# displayBoard-v2.net
KiCad netlist of a schematic drawn in EAGLE
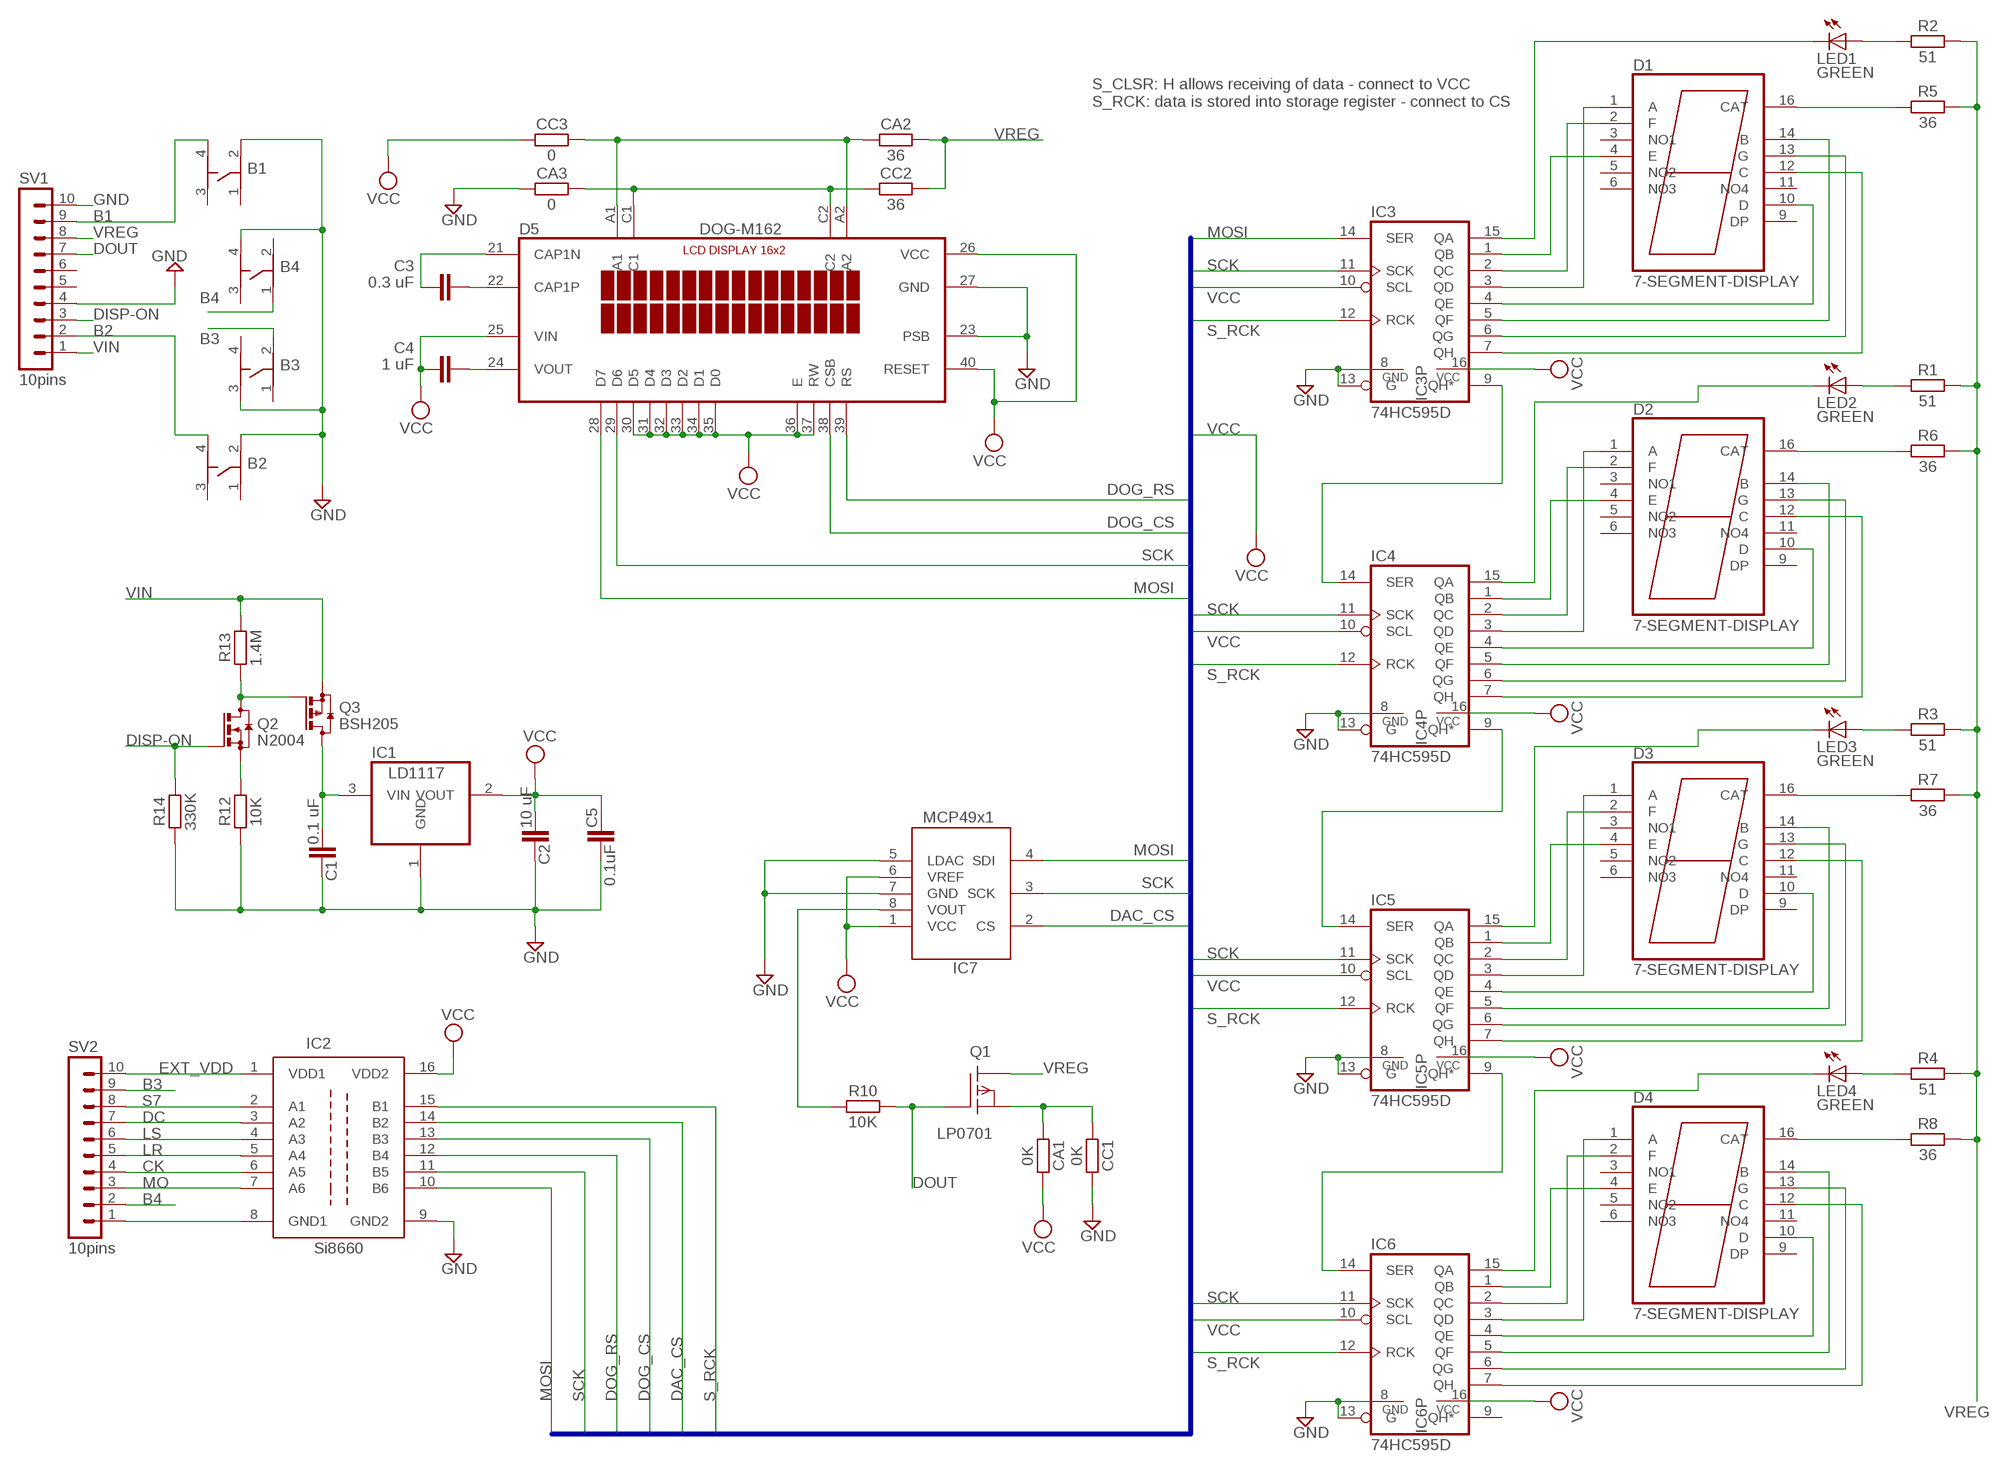
[diagram p0: schematic, sheet 1]

(export (version "E")
  (design (tool "Eeschema 10.0.6"))
  (components
    (comp (ref "B1")
      (value "BUTTON-D6X")
      (footprint "eagle-import:BUTTON-D6X")
      (libsource (lib "eagle-import") (part "BUTTON-D6X"))
    )
    (comp (ref "B2")
      (value "BUTTON-D6X")
      (footprint "eagle-import:BUTTON-D6X")
      (libsource (lib "eagle-import") (part "BUTTON-D6X"))
    )
    (comp (ref "B3")
      (value "BUTTON-D6X")
      (footprint "eagle-import:BUTTON-D6X")
      (libsource (lib "eagle-import") (part "BUTTON-D6X"))
    )
    (comp (ref "B4")
      (value "BUTTON-D6X")
      (footprint "eagle-import:BUTTON-D6X")
      (libsource (lib "eagle-import") (part "BUTTON-D6X"))
    )
    (comp (ref "C1")
      (value "0.1 uF")
      (footprint "eagle-import:C1206")
      (libsource (lib "eagle-import") (part "C-EUC1206"))
    )
    (comp (ref "C2")
      (value "10 uF")
      (footprint "eagle-import:C1206")
      (libsource (lib "eagle-import") (part "C-EUC1206"))
    )
    (comp (ref "C3")
      (value "0.3 uF")
      (footprint "eagle-import:C1206")
      (libsource (lib "eagle-import") (part "C-EUC1206"))
    )
    (comp (ref "C4")
      (value "1 uF")
      (footprint "eagle-import:C1206")
      (libsource (lib "eagle-import") (part "C-EUC1206"))
    )
    (comp (ref "C5")
      (value "0.1uF")
      (footprint "eagle-import:C1206")
      (libsource (lib "eagle-import") (part "C-EUC1206"))
    )
    (comp (ref "CA1")
      (value "0K")
      (footprint "eagle-import:R1206")
      (libsource (lib "eagle-import") (part "R-EU_R1206"))
    )
    (comp (ref "CA2")
      (value "36")
      (footprint "eagle-import:R1206")
      (libsource (lib "eagle-import") (part "R-EU_R1206"))
    )
    (comp (ref "CA3")
      (value "0")
      (footprint "eagle-import:R1206")
      (libsource (lib "eagle-import") (part "R-EU_R1206"))
    )
    (comp (ref "CC1")
      (value "0K")
      (footprint "eagle-import:R1206")
      (libsource (lib "eagle-import") (part "R-EU_R1206"))
    )
    (comp (ref "CC2")
      (value "36")
      (footprint "eagle-import:R1206")
      (libsource (lib "eagle-import") (part "R-EU_R1206"))
    )
    (comp (ref "CC3")
      (value "0")
      (footprint "eagle-import:R1206")
      (libsource (lib "eagle-import") (part "R-EU_R1206"))
    )
    (comp (ref "D1")
      (value "7-SEGMENT-DISPLAY")
      (footprint "eagle-import:LDS-A812")
      (libsource (lib "eagle-import") (part "7-SEGMENT-DISPLAY"))
    )
    (comp (ref "D2")
      (value "7-SEGMENT-DISPLAY")
      (footprint "eagle-import:LDS-A812")
      (libsource (lib "eagle-import") (part "7-SEGMENT-DISPLAY"))
    )
    (comp (ref "D3")
      (value "7-SEGMENT-DISPLAY")
      (footprint "eagle-import:LDS-A812")
      (libsource (lib "eagle-import") (part "7-SEGMENT-DISPLAY"))
    )
    (comp (ref "D4")
      (value "7-SEGMENT-DISPLAY")
      (footprint "eagle-import:LDS-A812")
      (libsource (lib "eagle-import") (part "7-SEGMENT-DISPLAY"))
    )
    (comp (ref "D5")
      (value "DOG-M162")
      (footprint "eagle-import:DOGM162")
      (libsource (lib "eagle-import") (part "DOG-M162"))
    )
    (comp (ref "IC1")
      (value "LD1117")
      (footprint "eagle-import:SOT223")
      (fields (field (name "MPN") "REG1117"))
      (libsource (lib "eagle-import") (part "REG1117"))
    )
    (comp (ref "IC2")
      (value "SI-8660")
      (footprint "eagle-import:SOP-16")
      (libsource (lib "eagle-import") (part "SI-8660"))
    )
    (comp (ref "IC3")
      (value "74HC595D")
      (footprint "eagle-import:SO16")
      (libsource (lib "eagle-import") (part "74595DHC"))
    )
    (comp (ref "IC4")
      (value "74HC595D")
      (footprint "eagle-import:SO16")
      (libsource (lib "eagle-import") (part "74595DHC"))
    )
    (comp (ref "IC5")
      (value "74HC595D")
      (footprint "eagle-import:SO16")
      (libsource (lib "eagle-import") (part "74595DHC"))
    )
    (comp (ref "IC6")
      (value "74HC595D")
      (footprint "eagle-import:SO16")
      (libsource (lib "eagle-import") (part "74595DHC"))
    )
    (comp (ref "IC7")
      (value "MCP4921")
      (footprint "eagle-import:MSOP-8")
      (libsource (lib "eagle-import") (part "MCP4901"))
    )
    (comp (ref "LED1")
      (value "GREEN")
      (footprint "eagle-import:LED3MM")
      (libsource (lib "eagle-import") (part "LED3MM"))
    )
    (comp (ref "LED2")
      (value "GREEN")
      (footprint "eagle-import:LED3MM")
      (libsource (lib "eagle-import") (part "LED3MM"))
    )
    (comp (ref "LED3")
      (value "GREEN")
      (footprint "eagle-import:LED3MM")
      (libsource (lib "eagle-import") (part "LED3MM"))
    )
    (comp (ref "LED4")
      (value "GREEN")
      (footprint "eagle-import:LED3MM")
      (libsource (lib "eagle-import") (part "LED3MM"))
    )
    (comp (ref "Q1")
      (value "LP0701")
      (footprint "eagle-import:TO-92")
      (libsource (lib "eagle-import") (part "LP0701N3"))
    )
    (comp (ref "Q2")
      (value "N2004")
      (footprint "eagle-import:SOT23")
      (libsource (lib "eagle-import") (part "BSS123"))
    )
    (comp (ref "Q3")
      (value "BSH205")
      (footprint "eagle-import:SOT23")
      (libsource (lib "eagle-import") (part "BSS84"))
    )
    (comp (ref "R1")
      (value "51")
      (footprint "eagle-import:R1206")
      (libsource (lib "eagle-import") (part "R-EU_R1206"))
    )
    (comp (ref "R2")
      (value "51")
      (footprint "eagle-import:R1206")
      (libsource (lib "eagle-import") (part "R-EU_R1206"))
    )
    (comp (ref "R3")
      (value "51")
      (footprint "eagle-import:R1206")
      (libsource (lib "eagle-import") (part "R-EU_R1206"))
    )
    (comp (ref "R4")
      (value "51")
      (footprint "eagle-import:R1206")
      (libsource (lib "eagle-import") (part "R-EU_R1206"))
    )
    (comp (ref "R5")
      (value "36")
      (footprint "eagle-import:R1206")
      (libsource (lib "eagle-import") (part "R-EU_R1206"))
    )
    (comp (ref "R6")
      (value "36")
      (footprint "eagle-import:R1206")
      (libsource (lib "eagle-import") (part "R-EU_R1206"))
    )
    (comp (ref "R7")
      (value "36")
      (footprint "eagle-import:R1206")
      (libsource (lib "eagle-import") (part "R-EU_R1206"))
    )
    (comp (ref "R8")
      (value "36")
      (footprint "eagle-import:R1206")
      (libsource (lib "eagle-import") (part "R-EU_R1206"))
    )
    (comp (ref "R10")
      (value "10K")
      (footprint "eagle-import:R1206")
      (libsource (lib "eagle-import") (part "R-EU_R1206"))
    )
    (comp (ref "R12")
      (value "10K")
      (footprint "eagle-import:R1206")
      (libsource (lib "eagle-import") (part "R-EU_R1206"))
    )
    (comp (ref "R13")
      (value "1.4M")
      (footprint "eagle-import:R1206")
      (libsource (lib "eagle-import") (part "R-EU_R1206"))
    )
    (comp (ref "R14")
      (value "330K")
      (footprint "eagle-import:R1206")
      (libsource (lib "eagle-import") (part "R-EU_R1206"))
    )
    (comp (ref "SV1")
      (value "10pins")
      (footprint "eagle-import:MA10-1")
      (libsource (lib "eagle-import") (part "MA10-1"))
    )
    (comp (ref "SV2")
      (value "10pins")
      (footprint "eagle-import:MA10-1")
      (libsource (lib "eagle-import") (part "MA10-1"))
    )
  )
  (nets
    (net (code "1") (name "/B1") (class "Default")
      (node (ref "B1") (pin "4") (pinfunction "4_4") (pintype "bidirectional"))
      (node (ref "SV1") (pin "9") (pinfunction "9_9") (pintype "passive"))
    )
    (net (code "2") (name "/B2") (class "Default")
      (node (ref "B2") (pin "4") (pinfunction "4_4") (pintype "bidirectional"))
      (node (ref "SV1") (pin "2") (pinfunction "2_2") (pintype "passive"))
    )
    (net (code "3") (name "/B3") (class "Default")
      (node (ref "B3") (pin "2") (pinfunction "2_2") (pintype "bidirectional"))
      (node (ref "SV2") (pin "9") (pinfunction "9_9") (pintype "passive"))
    )
    (net (code "4") (name "/B4") (class "Default")
      (node (ref "B4") (pin "1") (pinfunction "1_1") (pintype "bidirectional"))
      (node (ref "SV2") (pin "2") (pinfunction "2_2") (pintype "passive"))
    )
    (net (code "5") (name "/CK") (class "Default")
      (node (ref "IC2") (pin "6") (pinfunction "A5_6") (pintype "bidirectional"))
      (node (ref "SV2") (pin "4") (pinfunction "4_4") (pintype "passive"))
    )
    (net (code "6") (name "/DAC_CS") (class "Default")
      (node (ref "IC2") (pin "14") (pinfunction "B2_14") (pintype "bidirectional"))
      (node (ref "IC7") (pin "2") (pinfunction "CS_2") (pintype "bidirectional"))
    )
    (net (code "7") (name "/DC") (class "Default")
      (node (ref "IC2") (pin "3") (pinfunction "A2_3") (pintype "bidirectional"))
      (node (ref "SV2") (pin "7") (pinfunction "7_7") (pintype "passive"))
    )
    (net (code "8") (name "/DISP-ON") (class "Default")
      (node (ref "Q2") (pin "1") (pinfunction "G_1") (pintype "passive"))
      (node (ref "R14") (pin "2") (pinfunction "2_2") (pintype "passive"))
      (node (ref "SV1") (pin "3") (pinfunction "3_3") (pintype "passive"))
    )
    (net (code "9") (name "/DOG_CS") (class "Default")
      (node (ref "D5") (pin "38") (pinfunction "CSB_38") (pintype "bidirectional"))
      (node (ref "IC2") (pin "13") (pinfunction "B3_13") (pintype "bidirectional"))
    )
    (net (code "10") (name "/DOG_RS") (class "Default")
      (node (ref "D5") (pin "39") (pinfunction "RS_39") (pintype "bidirectional"))
      (node (ref "IC2") (pin "12") (pinfunction "B4_12") (pintype "bidirectional"))
    )
    (net (code "11") (name "/DOUT") (class "Default")
      (node (ref "Q1") (pin "2") (pinfunction "G_2") (pintype "passive"))
      (node (ref "R10") (pin "2") (pinfunction "2_2") (pintype "passive"))
      (node (ref "SV1") (pin "7") (pinfunction "7_7") (pintype "passive"))
    )
    (net (code "12") (name "/EXT_VDD") (class "Default")
      (node (ref "IC2") (pin "1") (pinfunction "VDD1_1") (pintype "bidirectional"))
      (node (ref "SV2") (pin "10") (pinfunction "10_10") (pintype "passive"))
    )
    (net (code "13") (name "/LR") (class "Default")
      (node (ref "IC2") (pin "5") (pinfunction "A4_5") (pintype "bidirectional"))
      (node (ref "SV2") (pin "5") (pinfunction "5_5") (pintype "passive"))
    )
    (net (code "14") (name "/LS") (class "Default")
      (node (ref "IC2") (pin "4") (pinfunction "A3_4") (pintype "bidirectional"))
      (node (ref "SV2") (pin "6") (pinfunction "6_6") (pintype "passive"))
    )
    (net (code "15") (name "/MO") (class "Default")
      (node (ref "IC2") (pin "7") (pinfunction "A6_7") (pintype "bidirectional"))
      (node (ref "SV2") (pin "3") (pinfunction "3_3") (pintype "passive"))
    )
    (net (code "16") (name "/MOSI") (class "Default")
      (node (ref "D5") (pin "28") (pinfunction "D7_28") (pintype "bidirectional"))
      (node (ref "IC2") (pin "10") (pinfunction "B6_10") (pintype "bidirectional"))
      (node (ref "IC3") (pin "14") (pinfunction "SER_14") (pintype "input"))
      (node (ref "IC7") (pin "4") (pinfunction "SDI_4") (pintype "bidirectional"))
    )
    (net (code "17") (name "/S7") (class "Default")
      (node (ref "IC2") (pin "2") (pinfunction "A1_2") (pintype "bidirectional"))
      (node (ref "SV2") (pin "8") (pinfunction "8_8") (pintype "passive"))
    )
    (net (code "18") (name "/SCK") (class "Default")
      (node (ref "D5") (pin "29") (pinfunction "D6_29") (pintype "bidirectional"))
      (node (ref "IC2") (pin "11") (pinfunction "B5_11") (pintype "bidirectional"))
      (node (ref "IC3") (pin "11") (pinfunction "SCK_11") (pintype "input"))
      (node (ref "IC4") (pin "11") (pinfunction "SCK_11") (pintype "input"))
      (node (ref "IC5") (pin "11") (pinfunction "SCK_11") (pintype "input"))
      (node (ref "IC6") (pin "11") (pinfunction "SCK_11") (pintype "input"))
      (node (ref "IC7") (pin "3") (pinfunction "SCK_3") (pintype "bidirectional"))
    )
    (net (code "19") (name "/S_RCK") (class "Default")
      (node (ref "IC2") (pin "15") (pinfunction "B1_15") (pintype "bidirectional"))
      (node (ref "IC3") (pin "12") (pinfunction "RCK_12") (pintype "input"))
      (node (ref "IC4") (pin "12") (pinfunction "RCK_12") (pintype "input"))
      (node (ref "IC5") (pin "12") (pinfunction "RCK_12") (pintype "input"))
      (node (ref "IC6") (pin "12") (pinfunction "RCK_12") (pintype "input"))
    )
    (net (code "20") (name "/VIN") (class "Default")
      (node (ref "Q3") (pin "2") (pinfunction "S_2") (pintype "passive"))
      (node (ref "R13") (pin "2") (pinfunction "2_2") (pintype "passive"))
      (node (ref "SV1") (pin "1") (pinfunction "1_1") (pintype "passive"))
    )
    (net (code "21") (name "/VREG") (class "Default")
      (node (ref "CA2") (pin "2") (pinfunction "2_2") (pintype "passive"))
      (node (ref "CC2") (pin "2") (pinfunction "2_2") (pintype "passive"))
      (node (ref "Q1") (pin "3") (pinfunction "D_3") (pintype "passive"))
      (node (ref "R1") (pin "2") (pinfunction "2_2") (pintype "passive"))
      (node (ref "R2") (pin "2") (pinfunction "2_2") (pintype "passive"))
      (node (ref "R3") (pin "2") (pinfunction "2_2") (pintype "passive"))
      (node (ref "R4") (pin "2") (pinfunction "2_2") (pintype "passive"))
      (node (ref "R5") (pin "2") (pinfunction "2_2") (pintype "passive"))
      (node (ref "R6") (pin "2") (pinfunction "2_2") (pintype "passive"))
      (node (ref "R7") (pin "2") (pinfunction "2_2") (pintype "passive"))
      (node (ref "R8") (pin "2") (pinfunction "2_2") (pintype "passive"))
      (node (ref "SV1") (pin "8") (pinfunction "8_8") (pintype "passive"))
    )
    (net (code "22") (name "GND") (class "Default")
      (node (ref "B1") (pin "2") (pinfunction "2_2") (pintype "bidirectional"))
      (node (ref "B2") (pin "2") (pinfunction "2_2") (pintype "bidirectional"))
      (node (ref "B3") (pin "3") (pinfunction "3_3") (pintype "bidirectional"))
      (node (ref "B4") (pin "4") (pinfunction "4_4") (pintype "bidirectional"))
      (node (ref "C1") (pin "1") (pinfunction "1_1") (pintype "passive"))
      (node (ref "C2") (pin "1") (pinfunction "1_1") (pintype "passive"))
      (node (ref "C5") (pin "2") (pinfunction "2_2") (pintype "passive"))
      (node (ref "CA3") (pin "1") (pinfunction "1_1") (pintype "passive"))
      (node (ref "CC1") (pin "2") (pinfunction "2_2") (pintype "passive"))
      (node (ref "D5") (pin "23") (pinfunction "PSB_23") (pintype "bidirectional"))
      (node (ref "D5") (pin "27") (pinfunction "GND_27") (pintype "power_in"))
      (node (ref "IC1") (pin "1") (pinfunction "GND_1") (pintype "power_in"))
      (node (ref "IC2") (pin "9") (pinfunction "GND2_9") (pintype "bidirectional"))
      (node (ref "IC3") (pin "13") (pinfunction "G_13") (pintype "input"))
      (node (ref "IC3") (pin "8") (pinfunction "GND_8") (pintype "power_in"))
      (node (ref "IC4") (pin "13") (pinfunction "G_13") (pintype "input"))
      (node (ref "IC4") (pin "8") (pinfunction "GND_8") (pintype "power_in"))
      (node (ref "IC5") (pin "13") (pinfunction "G_13") (pintype "input"))
      (node (ref "IC5") (pin "8") (pinfunction "GND_8") (pintype "power_in"))
      (node (ref "IC6") (pin "13") (pinfunction "G_13") (pintype "input"))
      (node (ref "IC6") (pin "8") (pinfunction "GND_8") (pintype "power_in"))
      (node (ref "IC7") (pin "5") (pinfunction "LDAC_5") (pintype "bidirectional"))
      (node (ref "IC7") (pin "7") (pinfunction "GND_7") (pintype "power_in"))
      (node (ref "R12") (pin "1") (pinfunction "1_1") (pintype "passive"))
      (node (ref "R14") (pin "1") (pinfunction "1_1") (pintype "passive"))
      (node (ref "SV1") (pin "10") (pinfunction "10_10") (pintype "passive"))
      (node (ref "SV1") (pin "4") (pinfunction "4_4") (pintype "passive"))
    )
    (net (code "23") (name "Net-(CA2-Pad1)") (class "Default")
      (node (ref "CA2") (pin "1") (pinfunction "1_1") (pintype "passive"))
      (node (ref "CC3") (pin "2") (pinfunction "2_2") (pintype "passive"))
      (node (ref "D5") (pin "A1") (pinfunction "A1_A1") (pintype "bidirectional"))
      (node (ref "D5") (pin "A2") (pinfunction "A2_A2") (pintype "bidirectional"))
    )
    (net (code "24") (name "Net-(CA3-Pad2)") (class "Default")
      (node (ref "CA3") (pin "2") (pinfunction "2_2") (pintype "passive"))
      (node (ref "CC2") (pin "1") (pinfunction "1_1") (pintype "passive"))
      (node (ref "D5") (pin "C1") (pinfunction "C1_C1") (pintype "bidirectional"))
      (node (ref "D5") (pin "C2") (pinfunction "C2_C2") (pintype "bidirectional"))
    )
    (net (code "25") (name "Net-(D1-A)") (class "Default")
      (node (ref "D1") (pin "1") (pinfunction "A_1") (pintype "input"))
      (node (ref "IC3") (pin "3") (pinfunction "QD_3") (pintype "tri_state"))
    )
    (net (code "26") (name "Net-(D1-B)") (class "Default")
      (node (ref "D1") (pin "14") (pinfunction "B_14") (pintype "input"))
      (node (ref "IC3") (pin "5") (pinfunction "QF_5") (pintype "tri_state"))
    )
    (net (code "27") (name "Net-(D1-C)") (class "Default")
      (node (ref "D1") (pin "12") (pinfunction "C_12") (pintype "input"))
      (node (ref "IC3") (pin "7") (pinfunction "QH_7") (pintype "tri_state"))
    )
    (net (code "28") (name "Net-(D1-CAT)") (class "Default")
      (node (ref "D1") (pin "16") (pinfunction "CAT_16") (pintype "bidirectional"))
      (node (ref "R5") (pin "1") (pinfunction "1_1") (pintype "passive"))
    )
    (net (code "29") (name "Net-(D1-D)") (class "Default")
      (node (ref "D1") (pin "10") (pinfunction "D_10") (pintype "input"))
      (node (ref "IC3") (pin "4") (pinfunction "QE_4") (pintype "tri_state"))
    )
    (net (code "30") (name "Net-(D1-E)") (class "Default")
      (node (ref "D1") (pin "4") (pinfunction "E_4") (pintype "input"))
      (node (ref "IC3") (pin "1") (pinfunction "QB_1") (pintype "tri_state"))
    )
    (net (code "31") (name "Net-(D1-F)") (class "Default")
      (node (ref "D1") (pin "2") (pinfunction "F_2") (pintype "input"))
      (node (ref "IC3") (pin "2") (pinfunction "QC_2") (pintype "tri_state"))
    )
    (net (code "32") (name "Net-(D1-G)") (class "Default")
      (node (ref "D1") (pin "13") (pinfunction "G_13") (pintype "input"))
      (node (ref "IC3") (pin "6") (pinfunction "QG_6") (pintype "tri_state"))
    )
    (net (code "33") (name "Net-(D2-A)") (class "Default")
      (node (ref "D2") (pin "1") (pinfunction "A_1") (pintype "input"))
      (node (ref "IC4") (pin "3") (pinfunction "QD_3") (pintype "tri_state"))
    )
    (net (code "34") (name "Net-(D2-B)") (class "Default")
      (node (ref "D2") (pin "14") (pinfunction "B_14") (pintype "input"))
      (node (ref "IC4") (pin "5") (pinfunction "QF_5") (pintype "tri_state"))
    )
    (net (code "35") (name "Net-(D2-C)") (class "Default")
      (node (ref "D2") (pin "12") (pinfunction "C_12") (pintype "input"))
      (node (ref "IC4") (pin "7") (pinfunction "QH_7") (pintype "tri_state"))
    )
    (net (code "36") (name "Net-(D2-CAT)") (class "Default")
      (node (ref "D2") (pin "16") (pinfunction "CAT_16") (pintype "bidirectional"))
      (node (ref "R6") (pin "1") (pinfunction "1_1") (pintype "passive"))
    )
    (net (code "37") (name "Net-(D2-D)") (class "Default")
      (node (ref "D2") (pin "10") (pinfunction "D_10") (pintype "input"))
      (node (ref "IC4") (pin "4") (pinfunction "QE_4") (pintype "tri_state"))
    )
    (net (code "38") (name "Net-(D2-E)") (class "Default")
      (node (ref "D2") (pin "4") (pinfunction "E_4") (pintype "input"))
      (node (ref "IC4") (pin "1") (pinfunction "QB_1") (pintype "tri_state"))
    )
    (net (code "39") (name "Net-(D2-F)") (class "Default")
      (node (ref "D2") (pin "2") (pinfunction "F_2") (pintype "input"))
      (node (ref "IC4") (pin "2") (pinfunction "QC_2") (pintype "tri_state"))
    )
    (net (code "40") (name "Net-(D2-G)") (class "Default")
      (node (ref "D2") (pin "13") (pinfunction "G_13") (pintype "input"))
      (node (ref "IC4") (pin "6") (pinfunction "QG_6") (pintype "tri_state"))
    )
    (net (code "41") (name "Net-(D3-A)") (class "Default")
      (node (ref "D3") (pin "1") (pinfunction "A_1") (pintype "input"))
      (node (ref "IC5") (pin "3") (pinfunction "QD_3") (pintype "tri_state"))
    )
    (net (code "42") (name "Net-(D3-B)") (class "Default")
      (node (ref "D3") (pin "14") (pinfunction "B_14") (pintype "input"))
      (node (ref "IC5") (pin "5") (pinfunction "QF_5") (pintype "tri_state"))
    )
    (net (code "43") (name "Net-(D3-C)") (class "Default")
      (node (ref "D3") (pin "12") (pinfunction "C_12") (pintype "input"))
      (node (ref "IC5") (pin "7") (pinfunction "QH_7") (pintype "tri_state"))
    )
    (net (code "44") (name "Net-(D3-CAT)") (class "Default")
      (node (ref "D3") (pin "16") (pinfunction "CAT_16") (pintype "bidirectional"))
      (node (ref "R7") (pin "1") (pinfunction "1_1") (pintype "passive"))
    )
    (net (code "45") (name "Net-(D3-D)") (class "Default")
      (node (ref "D3") (pin "10") (pinfunction "D_10") (pintype "input"))
      (node (ref "IC5") (pin "4") (pinfunction "QE_4") (pintype "tri_state"))
    )
    (net (code "46") (name "Net-(D3-E)") (class "Default")
      (node (ref "D3") (pin "4") (pinfunction "E_4") (pintype "input"))
      (node (ref "IC5") (pin "1") (pinfunction "QB_1") (pintype "tri_state"))
    )
    (net (code "47") (name "Net-(D3-F)") (class "Default")
      (node (ref "D3") (pin "2") (pinfunction "F_2") (pintype "input"))
      (node (ref "IC5") (pin "2") (pinfunction "QC_2") (pintype "tri_state"))
    )
    (net (code "48") (name "Net-(D3-G)") (class "Default")
      (node (ref "D3") (pin "13") (pinfunction "G_13") (pintype "input"))
      (node (ref "IC5") (pin "6") (pinfunction "QG_6") (pintype "tri_state"))
    )
    (net (code "49") (name "Net-(D4-A)") (class "Default")
      (node (ref "D4") (pin "1") (pinfunction "A_1") (pintype "input"))
      (node (ref "IC6") (pin "3") (pinfunction "QD_3") (pintype "tri_state"))
    )
    (net (code "50") (name "Net-(D4-B)") (class "Default")
      (node (ref "D4") (pin "14") (pinfunction "B_14") (pintype "input"))
      (node (ref "IC6") (pin "5") (pinfunction "QF_5") (pintype "tri_state"))
    )
    (net (code "51") (name "Net-(D4-C)") (class "Default")
      (node (ref "D4") (pin "12") (pinfunction "C_12") (pintype "input"))
      (node (ref "IC6") (pin "7") (pinfunction "QH_7") (pintype "tri_state"))
    )
    (net (code "52") (name "Net-(D4-CAT)") (class "Default")
      (node (ref "D4") (pin "16") (pinfunction "CAT_16") (pintype "bidirectional"))
      (node (ref "R8") (pin "1") (pinfunction "1_1") (pintype "passive"))
    )
    (net (code "53") (name "Net-(D4-D)") (class "Default")
      (node (ref "D4") (pin "10") (pinfunction "D_10") (pintype "input"))
      (node (ref "IC6") (pin "4") (pinfunction "QE_4") (pintype "tri_state"))
    )
    (net (code "54") (name "Net-(D4-E)") (class "Default")
      (node (ref "D4") (pin "4") (pinfunction "E_4") (pintype "input"))
      (node (ref "IC6") (pin "1") (pinfunction "QB_1") (pintype "tri_state"))
    )
    (net (code "55") (name "Net-(D4-F)") (class "Default")
      (node (ref "D4") (pin "2") (pinfunction "F_2") (pintype "input"))
      (node (ref "IC6") (pin "2") (pinfunction "QC_2") (pintype "tri_state"))
    )
    (net (code "56") (name "Net-(D4-G)") (class "Default")
      (node (ref "D4") (pin "13") (pinfunction "G_13") (pintype "input"))
      (node (ref "IC6") (pin "6") (pinfunction "QG_6") (pintype "tri_state"))
    )
    (net (code "57") (name "Net-(D5-CAP1N)") (class "Default")
      (node (ref "C3") (pin "1") (pinfunction "1_1") (pintype "passive"))
      (node (ref "D5") (pin "21") (pinfunction "CAP1N_21") (pintype "bidirectional"))
    )
    (net (code "58") (name "Net-(D5-CAP1P)") (class "Default")
      (node (ref "C3") (pin "2") (pinfunction "2_2") (pintype "passive"))
      (node (ref "D5") (pin "22") (pinfunction "CAP1P_22") (pintype "bidirectional"))
    )
    (net (code "59") (name "Net-(D5-VOUT)") (class "Default")
      (node (ref "C4") (pin "1") (pinfunction "1_1") (pintype "passive"))
      (node (ref "D5") (pin "24") (pinfunction "VOUT_24") (pintype "bidirectional"))
    )
    (net (code "60") (name "Net-(IC1-VIN)") (class "Default")
      (node (ref "C1") (pin "2") (pinfunction "2_2") (pintype "passive"))
      (node (ref "IC1") (pin "3") (pinfunction "VIN_3") (pintype "input"))
      (node (ref "Q3") (pin "3") (pinfunction "D_3") (pintype "passive"))
    )
    (net (code "61") (name "Net-(IC2-GND1)") (class "Default")
      (node (ref "IC2") (pin "8") (pinfunction "GND1_8") (pintype "bidirectional"))
      (node (ref "SV2") (pin "1") (pinfunction "1_1") (pintype "passive"))
    )
    (net (code "62") (name "Net-(IC3A-QA)") (class "Default")
      (node (ref "IC3") (pin "15") (pinfunction "QA_15") (pintype "tri_state"))
      (node (ref "LED1") (pin "K") (pinfunction "C_K") (pintype "passive"))
    )
    (net (code "63") (name "Net-(IC3A-QH*)") (class "Default")
      (node (ref "IC3") (pin "9") (pinfunction "QH*_9") (pintype "tri_state"))
      (node (ref "IC4") (pin "14") (pinfunction "SER_14") (pintype "input"))
    )
    (net (code "64") (name "Net-(IC4A-QA)") (class "Default")
      (node (ref "IC4") (pin "15") (pinfunction "QA_15") (pintype "tri_state"))
      (node (ref "LED2") (pin "K") (pinfunction "C_K") (pintype "passive"))
    )
    (net (code "65") (name "Net-(IC4A-QH*)") (class "Default")
      (node (ref "IC4") (pin "9") (pinfunction "QH*_9") (pintype "tri_state"))
      (node (ref "IC5") (pin "14") (pinfunction "SER_14") (pintype "input"))
    )
    (net (code "66") (name "Net-(IC5A-QA)") (class "Default")
      (node (ref "IC5") (pin "15") (pinfunction "QA_15") (pintype "tri_state"))
      (node (ref "LED3") (pin "K") (pinfunction "C_K") (pintype "passive"))
    )
    (net (code "67") (name "Net-(IC5A-QH*)") (class "Default")
      (node (ref "IC5") (pin "9") (pinfunction "QH*_9") (pintype "tri_state"))
      (node (ref "IC6") (pin "14") (pinfunction "SER_14") (pintype "input"))
    )
    (net (code "68") (name "Net-(IC6A-QA)") (class "Default")
      (node (ref "IC6") (pin "15") (pinfunction "QA_15") (pintype "tri_state"))
      (node (ref "LED4") (pin "K") (pinfunction "C_K") (pintype "passive"))
    )
    (net (code "69") (name "Net-(IC7-VOUT)") (class "Default")
      (node (ref "IC7") (pin "8") (pinfunction "VOUT_8") (pintype "bidirectional"))
      (node (ref "R10") (pin "1") (pinfunction "1_1") (pintype "passive"))
    )
    (net (code "70") (name "Net-(LED1-PadA)") (class "Default")
      (node (ref "LED1") (pin "A") (pinfunction "A_A") (pintype "passive"))
      (node (ref "R2") (pin "1") (pinfunction "1_1") (pintype "passive"))
    )
    (net (code "71") (name "Net-(LED2-PadA)") (class "Default")
      (node (ref "LED2") (pin "A") (pinfunction "A_A") (pintype "passive"))
      (node (ref "R1") (pin "1") (pinfunction "1_1") (pintype "passive"))
    )
    (net (code "72") (name "Net-(LED3-PadA)") (class "Default")
      (node (ref "LED3") (pin "A") (pinfunction "A_A") (pintype "passive"))
      (node (ref "R3") (pin "1") (pinfunction "1_1") (pintype "passive"))
    )
    (net (code "73") (name "Net-(LED4-PadA)") (class "Default")
      (node (ref "LED4") (pin "A") (pinfunction "A_A") (pintype "passive"))
      (node (ref "R4") (pin "1") (pinfunction "1_1") (pintype "passive"))
    )
    (net (code "74") (name "Net-(Q1-S)") (class "Default")
      (node (ref "CA1") (pin "1") (pinfunction "1_1") (pintype "passive"))
      (node (ref "CC1") (pin "1") (pinfunction "1_1") (pintype "passive"))
      (node (ref "Q1") (pin "1") (pinfunction "S_1") (pintype "passive"))
    )
    (net (code "75") (name "Net-(Q2-D)") (class "Default")
      (node (ref "Q2") (pin "3") (pinfunction "D_3") (pintype "passive"))
      (node (ref "Q3") (pin "1") (pinfunction "G_1") (pintype "passive"))
      (node (ref "R13") (pin "1") (pinfunction "1_1") (pintype "passive"))
    )
    (net (code "76") (name "Net-(Q2-S)") (class "Default")
      (node (ref "Q2") (pin "2") (pinfunction "S_2") (pintype "passive"))
      (node (ref "R12") (pin "2") (pinfunction "2_2") (pintype "passive"))
    )
    (net (code "77") (name "VCC") (class "Default")
      (node (ref "C2") (pin "2") (pinfunction "2_2") (pintype "passive"))
      (node (ref "C4") (pin "2") (pinfunction "2_2") (pintype "passive"))
      (node (ref "C5") (pin "1") (pinfunction "1_1") (pintype "passive"))
      (node (ref "CA1") (pin "2") (pinfunction "2_2") (pintype "passive"))
      (node (ref "CC3") (pin "1") (pinfunction "1_1") (pintype "passive"))
      (node (ref "D5") (pin "25") (pinfunction "VIN_25") (pintype "bidirectional"))
      (node (ref "D5") (pin "26") (pinfunction "VCC_26") (pintype "power_in"))
      (node (ref "D5") (pin "30") (pinfunction "D5_30") (pintype "bidirectional"))
      (node (ref "D5") (pin "31") (pinfunction "D4_31") (pintype "bidirectional"))
      (node (ref "D5") (pin "32") (pinfunction "D3_32") (pintype "bidirectional"))
      (node (ref "D5") (pin "33") (pinfunction "D2_33") (pintype "bidirectional"))
      (node (ref "D5") (pin "34") (pinfunction "D1_34") (pintype "bidirectional"))
      (node (ref "D5") (pin "35") (pinfunction "D0_35") (pintype "bidirectional"))
      (node (ref "D5") (pin "36") (pinfunction "E_36") (pintype "bidirectional"))
      (node (ref "D5") (pin "37") (pinfunction "RW_37") (pintype "bidirectional"))
      (node (ref "D5") (pin "40") (pinfunction "RESET_40") (pintype "bidirectional"))
      (node (ref "IC1") (pin "2") (pinfunction "VOUT_2") (pintype "power_in"))
      (node (ref "IC2") (pin "16") (pinfunction "VDD2_16") (pintype "bidirectional"))
      (node (ref "IC3") (pin "10") (pinfunction "SCL_10") (pintype "input"))
      (node (ref "IC3") (pin "16") (pinfunction "VCC_16") (pintype "power_in"))
      (node (ref "IC4") (pin "10") (pinfunction "SCL_10") (pintype "input"))
      (node (ref "IC4") (pin "16") (pinfunction "VCC_16") (pintype "power_in"))
      (node (ref "IC5") (pin "10") (pinfunction "SCL_10") (pintype "input"))
      (node (ref "IC5") (pin "16") (pinfunction "VCC_16") (pintype "power_in"))
      (node (ref "IC6") (pin "10") (pinfunction "SCL_10") (pintype "input"))
      (node (ref "IC6") (pin "16") (pinfunction "VCC_16") (pintype "power_in"))
      (node (ref "IC7") (pin "1") (pinfunction "VCC_1") (pintype "power_in"))
      (node (ref "IC7") (pin "6") (pinfunction "VREF_6") (pintype "bidirectional"))
    )
    (net (code "78") (name "unconnected-(B1-Pad1)") (class "Default")
      (node (ref "B1") (pin "1") (pinfunction "1_1") (pintype "bidirectional"))
    )
    (net (code "79") (name "unconnected-(B1-Pad3)") (class "Default")
      (node (ref "B1") (pin "3") (pinfunction "3_3") (pintype "bidirectional"))
    )
    (net (code "80") (name "unconnected-(B2-Pad1)") (class "Default")
      (node (ref "B2") (pin "1") (pinfunction "1_1") (pintype "bidirectional"))
    )
    (net (code "81") (name "unconnected-(B2-Pad3)") (class "Default")
      (node (ref "B2") (pin "3") (pinfunction "3_3") (pintype "bidirectional"))
    )
    (net (code "82") (name "unconnected-(B3-Pad1)") (class "Default")
      (node (ref "B3") (pin "1") (pinfunction "1_1") (pintype "bidirectional"))
    )
    (net (code "83") (name "unconnected-(B3-Pad4)") (class "Default")
      (node (ref "B3") (pin "4") (pinfunction "4_4") (pintype "bidirectional"))
    )
    (net (code "84") (name "unconnected-(B4-Pad2)") (class "Default")
      (node (ref "B4") (pin "2") (pinfunction "2_2") (pintype "bidirectional"))
    )
    (net (code "85") (name "unconnected-(B4-Pad3)") (class "Default")
      (node (ref "B4") (pin "3") (pinfunction "3_3") (pintype "bidirectional"))
    )
    (net (code "86") (name "unconnected-(D1-DP-Pad9)") (class "Default")
      (node (ref "D1") (pin "9") (pinfunction "DP_9") (pintype "bidirectional"))
    )
    (net (code "87") (name "unconnected-(D1-NO1-Pad3)") (class "Default")
      (node (ref "D1") (pin "3") (pinfunction "NO1_3") (pintype "bidirectional"))
    )
    (net (code "88") (name "unconnected-(D1-NO2-Pad5)") (class "Default")
      (node (ref "D1") (pin "5") (pinfunction "NO2_5") (pintype "bidirectional"))
    )
    (net (code "89") (name "unconnected-(D1-NO3-Pad6)") (class "Default")
      (node (ref "D1") (pin "6") (pinfunction "NO3_6") (pintype "bidirectional"))
    )
    (net (code "90") (name "unconnected-(D1-NO4-Pad11)") (class "Default")
      (node (ref "D1") (pin "11") (pinfunction "NO4_11") (pintype "bidirectional"))
    )
    (net (code "91") (name "unconnected-(D2-DP-Pad9)") (class "Default")
      (node (ref "D2") (pin "9") (pinfunction "DP_9") (pintype "bidirectional"))
    )
    (net (code "92") (name "unconnected-(D2-NO1-Pad3)") (class "Default")
      (node (ref "D2") (pin "3") (pinfunction "NO1_3") (pintype "bidirectional"))
    )
    (net (code "93") (name "unconnected-(D2-NO2-Pad5)") (class "Default")
      (node (ref "D2") (pin "5") (pinfunction "NO2_5") (pintype "bidirectional"))
    )
    (net (code "94") (name "unconnected-(D2-NO3-Pad6)") (class "Default")
      (node (ref "D2") (pin "6") (pinfunction "NO3_6") (pintype "bidirectional"))
    )
    (net (code "95") (name "unconnected-(D2-NO4-Pad11)") (class "Default")
      (node (ref "D2") (pin "11") (pinfunction "NO4_11") (pintype "bidirectional"))
    )
    (net (code "96") (name "unconnected-(D3-DP-Pad9)") (class "Default")
      (node (ref "D3") (pin "9") (pinfunction "DP_9") (pintype "bidirectional"))
    )
    (net (code "97") (name "unconnected-(D3-NO1-Pad3)") (class "Default")
      (node (ref "D3") (pin "3") (pinfunction "NO1_3") (pintype "bidirectional"))
    )
    (net (code "98") (name "unconnected-(D3-NO2-Pad5)") (class "Default")
      (node (ref "D3") (pin "5") (pinfunction "NO2_5") (pintype "bidirectional"))
    )
    (net (code "99") (name "unconnected-(D3-NO3-Pad6)") (class "Default")
      (node (ref "D3") (pin "6") (pinfunction "NO3_6") (pintype "bidirectional"))
    )
    (net (code "100") (name "unconnected-(D3-NO4-Pad11)") (class "Default")
      (node (ref "D3") (pin "11") (pinfunction "NO4_11") (pintype "bidirectional"))
    )
    (net (code "101") (name "unconnected-(D4-DP-Pad9)") (class "Default")
      (node (ref "D4") (pin "9") (pinfunction "DP_9") (pintype "bidirectional"))
    )
    (net (code "102") (name "unconnected-(D4-NO1-Pad3)") (class "Default")
      (node (ref "D4") (pin "3") (pinfunction "NO1_3") (pintype "bidirectional"))
    )
    (net (code "103") (name "unconnected-(D4-NO2-Pad5)") (class "Default")
      (node (ref "D4") (pin "5") (pinfunction "NO2_5") (pintype "bidirectional"))
    )
    (net (code "104") (name "unconnected-(D4-NO3-Pad6)") (class "Default")
      (node (ref "D4") (pin "6") (pinfunction "NO3_6") (pintype "bidirectional"))
    )
    (net (code "105") (name "unconnected-(D4-NO4-Pad11)") (class "Default")
      (node (ref "D4") (pin "11") (pinfunction "NO4_11") (pintype "bidirectional"))
    )
    (net (code "106") (name "unconnected-(IC6A-QH*-Pad9)") (class "Default")
      (node (ref "IC6") (pin "9") (pinfunction "QH*_9") (pintype "tri_state"))
    )
    (net (code "107") (name "unconnected-(SV1-Pad5)") (class "Default")
      (node (ref "SV1") (pin "5") (pinfunction "5_5") (pintype "passive"))
    )
    (net (code "108") (name "unconnected-(SV1-Pad6)") (class "Default")
      (node (ref "SV1") (pin "6") (pinfunction "6_6") (pintype "passive"))
    )
  )
)
